# RFPIGW.net
KiCad netlist of a schematic drawn in EAGLE
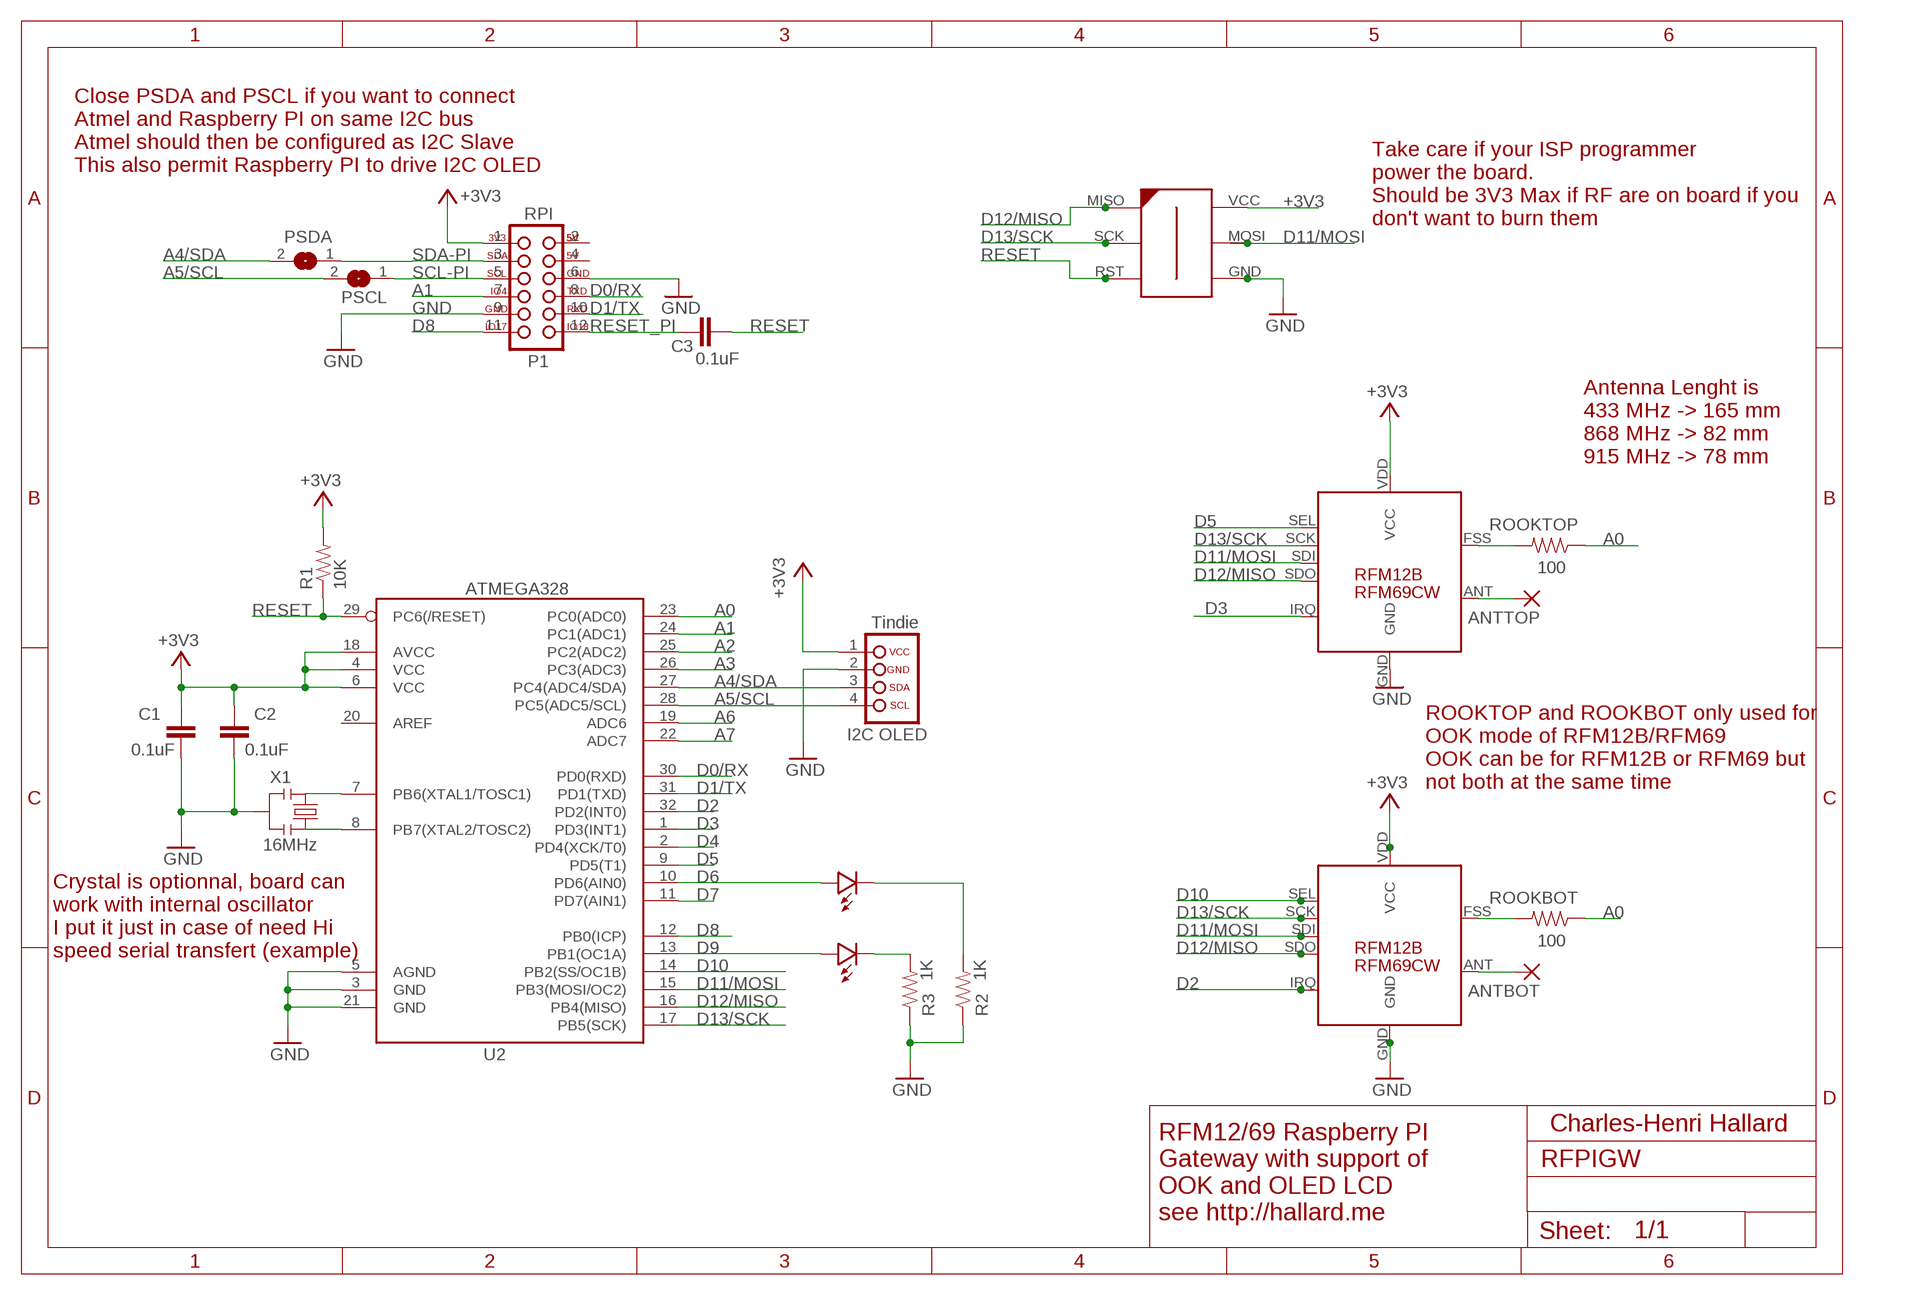
[diagram p0: schematic, sheet 1]

(export (version "E")
  (design (tool "Eeschema 10.0.6"))
  (components
    (comp (ref "ANTBOT")
      (value "1,6/0,8")
      (footprint "eagle-import:1,6_0,8")
      (libsource (lib "eagle-import") (part "1,6/0,8"))
    )
    (comp (ref "ANTTOP")
      (value "1,6/0,8")
      (footprint "eagle-import:1,6_0,8")
      (libsource (lib "eagle-import") (part "1,6/0,8"))
    )
    (comp (ref "C1")
      (value "0.1uF")
      (footprint "eagle-import:0805-CAP")
      (libsource (lib "eagle-import") (part "CAP0805-CAP"))
    )
    (comp (ref "C2")
      (value "0.1uF")
      (footprint "eagle-import:0805-CAP")
      (libsource (lib "eagle-import") (part "CAP0805-CAP"))
    )
    (comp (ref "C3")
      (value "0.1uF")
      (footprint "eagle-import:0805-CAP")
      (libsource (lib "eagle-import") (part "CAP0805-CAP"))
    )
    (comp (ref "LED1")
      (value "LED0805-LARGE")
      (footprint "eagle-import:0805-LED-LARGEPADS")
      (libsource (lib "eagle-import") (part "LED0805-LARGE"))
    )
    (comp (ref "LED2")
      (value "LED0805-LARGE")
      (footprint "eagle-import:0805-LED-LARGEPADS")
      (libsource (lib "eagle-import") (part "LED0805-LARGE"))
    )
    (comp (ref "OLED")
      (value "OLED_I2C_TINDIE")
      (footprint "eagle-import:1X04_NO_LOCK")
      (libsource (lib "eagle-import") (part "OLED_I2C_TINDIE"))
    )
    (comp (ref "PSCL")
      (value "SJ")
      (footprint "eagle-import:SJ")
      (libsource (lib "eagle-import") (part "SJ"))
    )
    (comp (ref "PSDA")
      (value "SJ")
      (footprint "eagle-import:SJ")
      (libsource (lib "eagle-import") (part "SJ"))
    )
    (comp (ref "R1")
      (value "10K")
      (footprint "eagle-import:0805-RES")
      (libsource (lib "eagle-import") (part "RESISTOR0805-RES"))
    )
    (comp (ref "R2")
      (value "1K")
      (footprint "eagle-import:0805-RES")
      (libsource (lib "eagle-import") (part "RESISTOR0805-RES"))
    )
    (comp (ref "R3")
      (value "1K")
      (footprint "eagle-import:0805-RES")
      (libsource (lib "eagle-import") (part "RESISTOR0805-RES"))
    )
    (comp (ref "ROOKBOT")
      (value "100")
      (footprint "eagle-import:0805-RES")
      (libsource (lib "eagle-import") (part "RESISTOR0805-RES"))
    )
    (comp (ref "ROOKTOP")
      (value "100")
      (footprint "eagle-import:0805-RES")
      (libsource (lib "eagle-import") (part "RESISTOR0805-RES"))
    )
    (comp (ref "U$1")
      (value "PI P1")
      (footprint "eagle-import:2X06_LOCK")
      (libsource (lib "eagle-import") (part "RASPBERRY_PI_2X6"))
    )
    (comp (ref "U$2")
      (value "RFM12B")
      (footprint "eagle-import:RFM12B-MINPADS")
      (libsource (lib "eagle-import") (part "RFM12B"))
    )
    (comp (ref "U$3")
      (value "RFM12B")
      (footprint "eagle-import:RFM12B-MINPADS")
      (libsource (lib "eagle-import") (part "RFM12B"))
    )
    (comp (ref "U$4")
      (value "AVR-ISP-6-EDGE")
      (footprint "eagle-import:6PAD_ISP")
      (libsource (lib "eagle-import") (part "AVR-ISP-6-EDGE"))
    )
    (comp (ref "U2")
      (value "ATMEGA328")
      (footprint "eagle-import:TQFP32-08")
      (libsource (lib "eagle-import") (part "ATMEGA168"))
    )
    (comp (ref "X1")
      (value "16MHz")
      (footprint "eagle-import:RESONATOR-SMD")
      (libsource (lib "eagle-import") (part "RESONATOR16MHZ"))
    )
  )
  (nets
    (net (code "1") (name "+3V3") (class "Default")
      (node (ref "C1") (pin "1") (pinfunction "1_1") (pintype "passive"))
      (node (ref "C2") (pin "1") (pinfunction "1_1") (pintype "passive"))
      (node (ref "OLED") (pin "1") (pinfunction "VCC_1") (pintype "power_in"))
      (node (ref "R1") (pin "2") (pinfunction "2_2") (pintype "passive"))
      (node (ref "U$1") (pin "1") (pinfunction "1_1") (pintype "power_in"))
      (node (ref "U$2") (pin "VDD") (pinfunction "VCC_VDD") (pintype "power_in"))
      (node (ref "U$3") (pin "VDD") (pinfunction "VCC_VDD") (pintype "power_in"))
      (node (ref "U$4") (pin "VCC") (pinfunction "P$6_VCC") (pintype "bidirectional"))
      (node (ref "U2") (pin "18") (pinfunction "AVCC_18") (pintype "bidirectional"))
      (node (ref "U2") (pin "4") (pinfunction "VCC_4") (pintype "bidirectional"))
      (node (ref "U2") (pin "6") (pinfunction "VCC_6") (pintype "bidirectional"))
    )
    (net (code "2") (name "/2") (class "Default")
      (node (ref "U$1") (pin "2") (pinfunction "2_2") (pintype "power_in"))
    )
    (net (code "3") (name "/4") (class "Default")
      (node (ref "U$1") (pin "4") (pinfunction "4_4") (pintype "power_in"))
    )
    (net (code "4") (name "/A0") (class "Default")
      (node (ref "ROOKBOT") (pin "1") (pinfunction "1_1") (pintype "passive"))
      (node (ref "ROOKTOP") (pin "1") (pinfunction "1_1") (pintype "passive"))
      (node (ref "U2") (pin "23") (pinfunction "PC0(ADC0)_23") (pintype "bidirectional"))
    )
    (net (code "5") (name "/A1") (class "Default")
      (node (ref "U$1") (pin "7") (pinfunction "7_7") (pintype "bidirectional"))
      (node (ref "U2") (pin "24") (pinfunction "PC1(ADC1)_24") (pintype "bidirectional"))
    )
    (net (code "6") (name "/A2") (class "Default")
      (node (ref "U2") (pin "25") (pinfunction "PC2(ADC2)_25") (pintype "bidirectional"))
    )
    (net (code "7") (name "/A3") (class "Default")
      (node (ref "U2") (pin "26") (pinfunction "PC3(ADC3)_26") (pintype "bidirectional"))
    )
    (net (code "8") (name "/A4{slash}SDA") (class "Default")
      (node (ref "OLED") (pin "3") (pinfunction "SDA_3") (pintype "bidirectional"))
      (node (ref "PSDA") (pin "2") (pinfunction "2_2") (pintype "passive"))
      (node (ref "U2") (pin "27") (pinfunction "PC4(ADC4/SDA)_27") (pintype "bidirectional"))
    )
    (net (code "9") (name "/A5{slash}SCL") (class "Default")
      (node (ref "OLED") (pin "4") (pinfunction "SCL_4") (pintype "bidirectional"))
      (node (ref "PSCL") (pin "2") (pinfunction "2_2") (pintype "passive"))
      (node (ref "U2") (pin "28") (pinfunction "PC5(ADC5/SCL)_28") (pintype "bidirectional"))
    )
    (net (code "10") (name "/A6") (class "Default")
      (node (ref "U2") (pin "19") (pinfunction "ADC6_19") (pintype "bidirectional"))
    )
    (net (code "11") (name "/A7") (class "Default")
      (node (ref "U2") (pin "22") (pinfunction "ADC7_22") (pintype "bidirectional"))
    )
    (net (code "12") (name "/D0{slash}RX") (class "Default")
      (node (ref "U$1") (pin "8") (pinfunction "8_8") (pintype "output"))
      (node (ref "U2") (pin "30") (pinfunction "PD0(RXD)_30") (pintype "bidirectional"))
    )
    (net (code "13") (name "/D1{slash}TX") (class "Default")
      (node (ref "U$1") (pin "10") (pinfunction "10_10") (pintype "input"))
      (node (ref "U2") (pin "31") (pinfunction "PD1(TXD)_31") (pintype "bidirectional"))
    )
    (net (code "14") (name "/D2") (class "Default")
      (node (ref "U$2") (pin "IRQ") (pinfunction "IRQ_IRQ") (pintype "open_collector"))
      (node (ref "U2") (pin "32") (pinfunction "PD2(INT0)_32") (pintype "bidirectional"))
    )
    (net (code "15") (name "/D3") (class "Default")
      (node (ref "U$3") (pin "IRQ") (pinfunction "IRQ_IRQ") (pintype "open_collector"))
      (node (ref "U2") (pin "1") (pinfunction "PD3(INT1)_1") (pintype "bidirectional"))
    )
    (net (code "16") (name "/D4") (class "Default")
      (node (ref "U2") (pin "2") (pinfunction "PD4(XCK/T0)_2") (pintype "bidirectional"))
    )
    (net (code "17") (name "/D5") (class "Default")
      (node (ref "U$3") (pin "SEL") (pinfunction "SEL_SEL") (pintype "input"))
      (node (ref "U2") (pin "9") (pinfunction "PD5(T1)_9") (pintype "bidirectional"))
    )
    (net (code "18") (name "/D6") (class "Default")
      (node (ref "LED2") (pin "PLUS") (pinfunction "PLUS_PLUS") (pintype "passive"))
      (node (ref "U2") (pin "10") (pinfunction "PD6(AIN0)_10") (pintype "bidirectional"))
    )
    (net (code "19") (name "/D7") (class "Default")
      (node (ref "U2") (pin "11") (pinfunction "PD7(AIN1)_11") (pintype "bidirectional"))
    )
    (net (code "20") (name "/D8") (class "Default")
      (node (ref "U$1") (pin "11") (pinfunction "11_11") (pintype "bidirectional"))
      (node (ref "U2") (pin "12") (pinfunction "PB0(ICP)_12") (pintype "bidirectional"))
    )
    (net (code "21") (name "/D9") (class "Default")
      (node (ref "LED1") (pin "PLUS") (pinfunction "PLUS_PLUS") (pintype "passive"))
      (node (ref "U2") (pin "13") (pinfunction "PB1(OC1A)_13") (pintype "bidirectional"))
    )
    (net (code "22") (name "/D10") (class "Default")
      (node (ref "U$2") (pin "SEL") (pinfunction "SEL_SEL") (pintype "input"))
      (node (ref "U2") (pin "14") (pinfunction "PB2(SS/OC1B)_14") (pintype "bidirectional"))
    )
    (net (code "23") (name "/D11{slash}MOSI") (class "Default")
      (node (ref "U$2") (pin "SDI") (pinfunction "SDI_SDI") (pintype "input"))
      (node (ref "U$3") (pin "SDI") (pinfunction "SDI_SDI") (pintype "input"))
      (node (ref "U$4") (pin "MOSI") (pinfunction "P$5_MOSI") (pintype "bidirectional"))
      (node (ref "U2") (pin "15") (pinfunction "PB3(MOSI/OC2)_15") (pintype "bidirectional"))
    )
    (net (code "24") (name "/D12{slash}MISO") (class "Default")
      (node (ref "U$2") (pin "SDO") (pinfunction "SDO_SDO") (pintype "output"))
      (node (ref "U$3") (pin "SDO") (pinfunction "SDO_SDO") (pintype "output"))
      (node (ref "U$4") (pin "MISO") (pinfunction "P$1_MISO") (pintype "bidirectional"))
      (node (ref "U2") (pin "16") (pinfunction "PB4(MISO)_16") (pintype "bidirectional"))
    )
    (net (code "25") (name "/D13{slash}SCK") (class "Default")
      (node (ref "U$2") (pin "SCK") (pinfunction "SCK_SCK") (pintype "input"))
      (node (ref "U$3") (pin "SCK") (pinfunction "SCK_SCK") (pintype "input"))
      (node (ref "U$4") (pin "SCK") (pinfunction "P$2_SCK") (pintype "bidirectional"))
      (node (ref "U2") (pin "17") (pinfunction "PB5(SCK)_17") (pintype "bidirectional"))
    )
    (net (code "26") (name "/RESET") (class "Default")
      (node (ref "C3") (pin "2") (pinfunction "2_2") (pintype "passive"))
      (node (ref "R1") (pin "1") (pinfunction "1_1") (pintype "passive"))
      (node (ref "U$4") (pin "RST") (pinfunction "P$3_RST") (pintype "bidirectional"))
      (node (ref "U2") (pin "29") (pinfunction "PC6(/RESET)_29") (pintype "bidirectional"))
    )
    (net (code "27") (name "/RESET_PI") (class "Default")
      (node (ref "C3") (pin "1") (pinfunction "1_1") (pintype "passive"))
      (node (ref "U$1") (pin "12") (pinfunction "12_12") (pintype "bidirectional"))
    )
    (net (code "28") (name "/SCL-PI") (class "Default")
      (node (ref "PSCL") (pin "1") (pinfunction "1_1") (pintype "passive"))
      (node (ref "U$1") (pin "5") (pinfunction "5_5") (pintype "bidirectional"))
    )
    (net (code "29") (name "/SDA-PI") (class "Default")
      (node (ref "PSDA") (pin "1") (pinfunction "1_1") (pintype "passive"))
      (node (ref "U$1") (pin "3") (pinfunction "3_3") (pintype "bidirectional"))
    )
    (net (code "30") (name "GND") (class "Default")
      (node (ref "C1") (pin "2") (pinfunction "2_2") (pintype "passive"))
      (node (ref "C2") (pin "2") (pinfunction "2_2") (pintype "passive"))
      (node (ref "OLED") (pin "2") (pinfunction "GND_2") (pintype "power_in"))
      (node (ref "R2") (pin "1") (pinfunction "1_1") (pintype "passive"))
      (node (ref "R3") (pin "1") (pinfunction "1_1") (pintype "passive"))
      (node (ref "U$1") (pin "6") (pinfunction "6_6") (pintype "passive"))
      (node (ref "U$1") (pin "9") (pinfunction "9_9") (pintype "passive"))
      (node (ref "U$2") (pin "GND") (pinfunction "GND_GND") (pintype "power_in"))
      (node (ref "U$3") (pin "GND") (pinfunction "GND_GND") (pintype "power_in"))
      (node (ref "U$4") (pin "GND") (pinfunction "P$4_GND") (pintype "bidirectional"))
      (node (ref "U2") (pin "21") (pinfunction "GND_21") (pintype "bidirectional"))
      (node (ref "U2") (pin "3") (pinfunction "GND_3") (pintype "bidirectional"))
      (node (ref "U2") (pin "5") (pinfunction "AGND_5") (pintype "bidirectional"))
      (node (ref "X1") (pin "2") (pinfunction "2_2") (pintype "passive"))
    )
    (net (code "31") (name "Net-(ANTBOT-P)") (class "Default")
      (node (ref "ANTBOT") (pin "1") (pinfunction "P_1") (pintype "passive"))
      (node (ref "U$2") (pin "ANT") (pinfunction "ANT_ANT") (pintype "passive"))
    )
    (net (code "32") (name "Net-(ANTTOP-P)") (class "Default")
      (node (ref "ANTTOP") (pin "1") (pinfunction "P_1") (pintype "passive"))
      (node (ref "U$3") (pin "ANT") (pinfunction "ANT_ANT") (pintype "passive"))
    )
    (net (code "33") (name "Net-(LED1-PadMINUS)") (class "Default")
      (node (ref "LED1") (pin "MINUS") (pinfunction "MINUS_MINUS") (pintype "passive"))
      (node (ref "R3") (pin "2") (pinfunction "2_2") (pintype "passive"))
    )
    (net (code "34") (name "Net-(LED2-PadMINUS)") (class "Default")
      (node (ref "LED2") (pin "MINUS") (pinfunction "MINUS_MINUS") (pintype "passive"))
      (node (ref "R2") (pin "2") (pinfunction "2_2") (pintype "passive"))
    )
    (net (code "35") (name "Net-(U$2-FFS)") (class "Default")
      (node (ref "ROOKBOT") (pin "2") (pinfunction "2_2") (pintype "passive"))
      (node (ref "U$2") (pin "FSS") (pinfunction "FFS_FSS") (pintype "bidirectional"))
    )
    (net (code "36") (name "Net-(U$3-FFS)") (class "Default")
      (node (ref "ROOKTOP") (pin "2") (pinfunction "2_2") (pintype "passive"))
      (node (ref "U$3") (pin "FSS") (pinfunction "FFS_FSS") (pintype "bidirectional"))
    )
    (net (code "37") (name "Net-(U2-PB6(XTAL1{slash}TOSC1))") (class "Default")
      (node (ref "U2") (pin "7") (pinfunction "PB6(XTAL1/TOSC1)_7") (pintype "bidirectional"))
      (node (ref "X1") (pin "1") (pinfunction "1_1") (pintype "passive"))
    )
    (net (code "38") (name "Net-(U2-PB7(XTAL2{slash}TOSC2))") (class "Default")
      (node (ref "U2") (pin "8") (pinfunction "PB7(XTAL2/TOSC2)_8") (pintype "bidirectional"))
      (node (ref "X1") (pin "3") (pinfunction "3_3") (pintype "passive"))
    )
    (net (code "39") (name "unconnected-(U2-AREF-Pad20)") (class "Default")
      (node (ref "U2") (pin "20") (pinfunction "AREF_20") (pintype "bidirectional"))
    )
  )
)
